# Keyfinder_MCU.net
KiCad netlist of a schematic drawn in Altium Designer
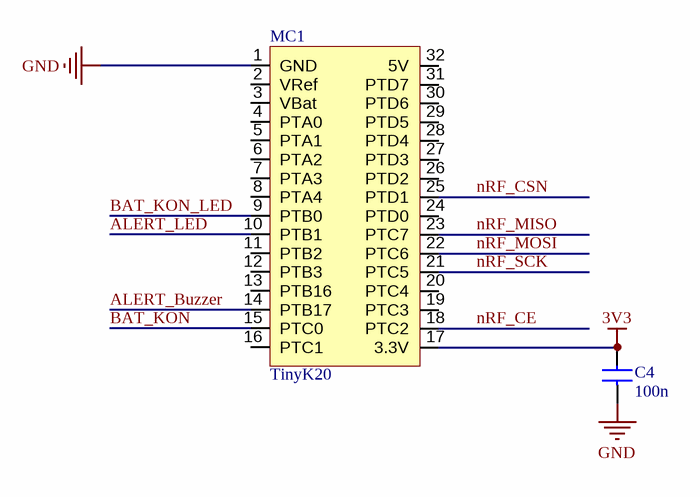
[diagram p0: Keyfinder_MCU.SchDoc]

(export (version "E")
  (design (tool "Eeschema 10.0.6"))
  (components
    (comp (ref "C4")
      (value "100n")
      (footprint "0805_C")
      (description "Normaler Kondensator")
      (libsource (lib "MainBoard") (part "C?"))
    )
    (comp (ref "MC1") (value "TinyK20") (footprint "DIP32") (libsource (lib "MainBoard") (part "TinyK20")))
  )
  (nets
    (net (code "1") (name "/ALERT_Buzzer") (class "Default")
      (node (ref "MC1") (pin "14") (pinfunction "PTB17_14") (pintype "passive"))
    )
    (net (code "2") (name "/ALERT_LED") (class "Default")
      (node (ref "MC1") (pin "10") (pinfunction "PTB1_10") (pintype "passive"))
    )
    (net (code "3") (name "/BAT_KON") (class "Default")
      (node (ref "MC1") (pin "15") (pinfunction "PTC0_15") (pintype "passive"))
    )
    (net (code "4") (name "/BAT_KON_LED") (class "Default")
      (node (ref "MC1") (pin "9") (pinfunction "PTB0_9") (pintype "passive"))
    )
    (net (code "5") (name "/nRF_CE") (class "Default")
      (node (ref "MC1") (pin "18") (pinfunction "PTC2_18") (pintype "passive"))
    )
    (net (code "6") (name "/nRF_CSN") (class "Default")
      (node (ref "MC1") (pin "25") (pinfunction "PTD1_25") (pintype "passive"))
    )
    (net (code "7") (name "/nRF_MISO") (class "Default")
      (node (ref "MC1") (pin "23") (pinfunction "PTC7_23") (pintype "passive"))
    )
    (net (code "8") (name "/nRF_MOSI") (class "Default")
      (node (ref "MC1") (pin "22") (pinfunction "PTC6_22") (pintype "passive"))
    )
    (net (code "9") (name "/nRF_SCK") (class "Default")
      (node (ref "MC1") (pin "21") (pinfunction "PTC5_21") (pintype "passive"))
    )
    (net (code "10") (name "3V3") (class "Default")
      (node (ref "C4") (pin "2") (pinfunction "2_2") (pintype "passive"))
      (node (ref "MC1") (pin "17") (pinfunction "3.3V_17") (pintype "passive"))
    )
    (net (code "11") (name "GND") (class "Default")
      (node (ref "C4") (pin "1") (pinfunction "1_1") (pintype "passive"))
      (node (ref "MC1") (pin "1") (pinfunction "GND_1") (pintype "passive"))
    )
    (net (code "12") (name "unconnected-(MC1-5V-Pad32)") (class "Default")
      (node (ref "MC1") (pin "32") (pinfunction "5V_32") (pintype "passive"))
    )
    (net (code "13") (name "unconnected-(MC1-PTA0-Pad4)") (class "Default")
      (node (ref "MC1") (pin "4") (pinfunction "PTA0_4") (pintype "passive"))
    )
    (net (code "14") (name "unconnected-(MC1-PTA1-Pad5)") (class "Default")
      (node (ref "MC1") (pin "5") (pinfunction "PTA1_5") (pintype "passive"))
    )
    (net (code "15") (name "unconnected-(MC1-PTA2-Pad6)") (class "Default")
      (node (ref "MC1") (pin "6") (pinfunction "PTA2_6") (pintype "passive"))
    )
    (net (code "16") (name "unconnected-(MC1-PTA3-Pad7)") (class "Default")
      (node (ref "MC1") (pin "7") (pinfunction "PTA3_7") (pintype "passive"))
    )
    (net (code "17") (name "unconnected-(MC1-PTA4-Pad8)") (class "Default")
      (node (ref "MC1") (pin "8") (pinfunction "PTA4_8") (pintype "passive"))
    )
    (net (code "18") (name "unconnected-(MC1-PTB2-Pad11)") (class "Default")
      (node (ref "MC1") (pin "11") (pinfunction "PTB2_11") (pintype "passive"))
    )
    (net (code "19") (name "unconnected-(MC1-PTB3-Pad12)") (class "Default")
      (node (ref "MC1") (pin "12") (pinfunction "PTB3_12") (pintype "passive"))
    )
    (net (code "20") (name "unconnected-(MC1-PTB16-Pad13)") (class "Default")
      (node (ref "MC1") (pin "13") (pinfunction "PTB16_13") (pintype "passive"))
    )
    (net (code "21") (name "unconnected-(MC1-PTC1-Pad16)") (class "Default")
      (node (ref "MC1") (pin "16") (pinfunction "PTC1_16") (pintype "passive"))
    )
    (net (code "22") (name "unconnected-(MC1-PTC3-Pad19)") (class "Default")
      (node (ref "MC1") (pin "19") (pinfunction "PTC3_19") (pintype "passive"))
    )
    (net (code "23") (name "unconnected-(MC1-PTC4-Pad20)") (class "Default")
      (node (ref "MC1") (pin "20") (pinfunction "PTC4_20") (pintype "passive"))
    )
    (net (code "24") (name "unconnected-(MC1-PTD0-Pad24)") (class "Default")
      (node (ref "MC1") (pin "24") (pinfunction "PTD0_24") (pintype "passive"))
    )
    (net (code "25") (name "unconnected-(MC1-PTD2-Pad26)") (class "Default")
      (node (ref "MC1") (pin "26") (pinfunction "PTD2_26") (pintype "passive"))
    )
    (net (code "26") (name "unconnected-(MC1-PTD3-Pad27)") (class "Default")
      (node (ref "MC1") (pin "27") (pinfunction "PTD3_27") (pintype "passive"))
    )
    (net (code "27") (name "unconnected-(MC1-PTD4-Pad28)") (class "Default")
      (node (ref "MC1") (pin "28") (pinfunction "PTD4_28") (pintype "passive"))
    )
    (net (code "28") (name "unconnected-(MC1-PTD5-Pad29)") (class "Default")
      (node (ref "MC1") (pin "29") (pinfunction "PTD5_29") (pintype "passive"))
    )
    (net (code "29") (name "unconnected-(MC1-PTD6-Pad30)") (class "Default")
      (node (ref "MC1") (pin "30") (pinfunction "PTD6_30") (pintype "passive"))
    )
    (net (code "30") (name "unconnected-(MC1-PTD7-Pad31)") (class "Default")
      (node (ref "MC1") (pin "31") (pinfunction "PTD7_31") (pintype "passive"))
    )
    (net (code "31") (name "unconnected-(MC1-VBat-Pad3)") (class "Default")
      (node (ref "MC1") (pin "3") (pinfunction "VBat_3") (pintype "passive"))
    )
    (net (code "32") (name "unconnected-(MC1-VRef-Pad2)") (class "Default")
      (node (ref "MC1") (pin "2") (pinfunction "VRef_2") (pintype "passive"))
    )
  )
)
